# Bankomart.net
KiCad netlist of a schematic drawn in EAGLE
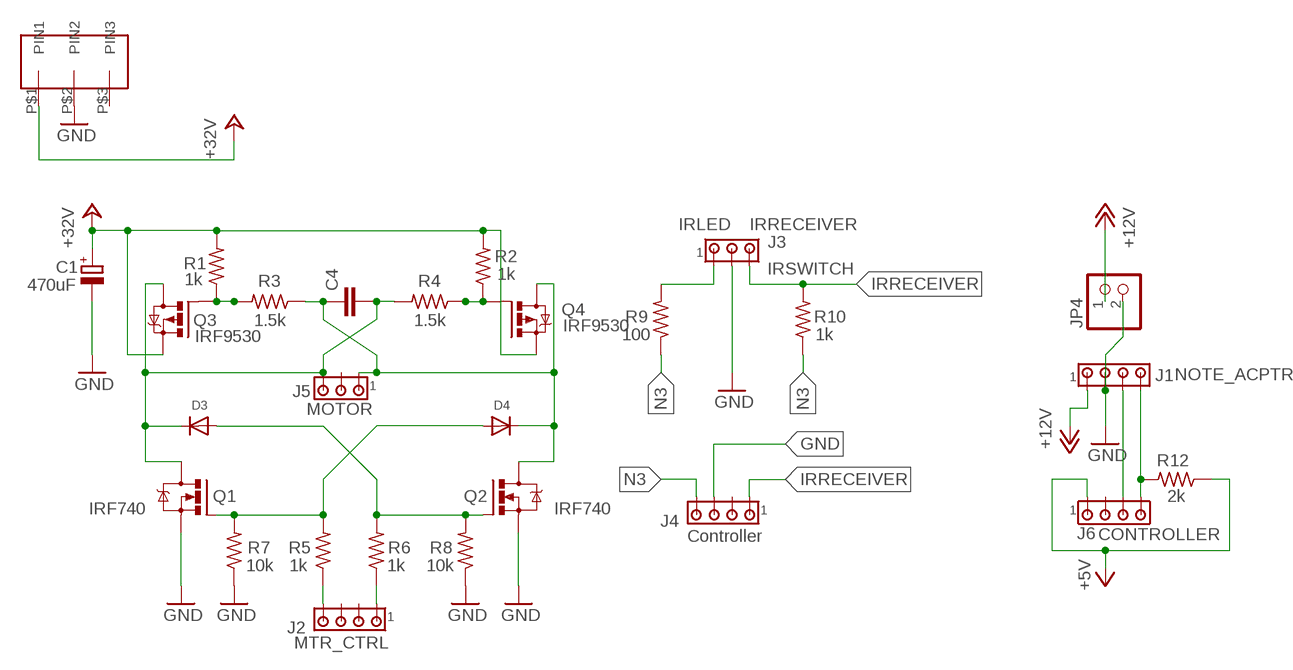
[diagram p0: schematic, sheet 1]

(export (version "E")
  (design (tool "Eeschema 10.0.6"))
  (components
    (comp (ref "C1")
      (value "470uF")
      (footprint "eagle-import:E7,5-18")
      (libsource (lib "eagle-import") (part "CPOL-EUE7.5-18"))
    )
    (comp (ref "C4")
      (value "C-EU050-025X075")
      (footprint "eagle-import:C050-025X075")
      (libsource (lib "eagle-import") (part "C-EU050-025X075"))
    )
    (comp (ref "D3")
      (value "DIODEDO-1N4148")
      (footprint "eagle-import:DO-1N4148")
      (libsource (lib "eagle-import") (part "DIODEDO-1N4148"))
    )
    (comp (ref "D4")
      (value "DIODEDO-1N4148")
      (footprint "eagle-import:DO-1N4148")
      (libsource (lib "eagle-import") (part "DIODEDO-1N4148"))
    )
    (comp (ref "J1")
      (value "NOTE_ACPTR")
      (footprint "eagle-import:10X04MTA")
      (libsource (lib "eagle-import") (part "MTA04-100"))
    )
    (comp (ref "J2")
      (value "MTR_CTRL")
      (footprint "eagle-import:10X04MTA")
      (libsource (lib "eagle-import") (part "MTA04-100"))
    )
    (comp (ref "J3")
      (value "IRSWITCH")
      (footprint "eagle-import:10X03MTA")
      (libsource (lib "eagle-import") (part "MTA03-100"))
    )
    (comp (ref "J4")
      (value "Controller")
      (footprint "eagle-import:10X04MTA")
      (libsource (lib "eagle-import") (part "MTA04-100"))
    )
    (comp (ref "J5")
      (value "MOTOR")
      (footprint "eagle-import:10X03MTA")
      (libsource (lib "eagle-import") (part "MTA03-100"))
    )
    (comp (ref "J6")
      (value "CONTROLLER")
      (footprint "eagle-import:10X04MTA")
      (libsource (lib "eagle-import") (part "MTA04-100"))
    )
    (comp (ref "JP4")
      (value "PINHD-1X2")
      (footprint "eagle-import:1X02")
      (libsource (lib "eagle-import") (part "PINHD-1X2"))
    )
    (comp (ref "Q1")
      (value "IRF740")
      (footprint "eagle-import:TO220BV")
      (libsource (lib "eagle-import") (part "IRF740"))
    )
    (comp (ref "Q2")
      (value "IRF740")
      (footprint "eagle-import:TO220BV")
      (libsource (lib "eagle-import") (part "IRF740"))
    )
    (comp (ref "Q3")
      (value "IRF9530")
      (footprint "eagle-import:TO220BV")
      (libsource (lib "eagle-import") (part "IRF9530"))
    )
    (comp (ref "Q4")
      (value "IRF9530")
      (footprint "eagle-import:TO220BV")
      (libsource (lib "eagle-import") (part "IRF9530"))
    )
    (comp (ref "R1")
      (value "1k")
      (footprint "eagle-import:0207_10")
      (libsource (lib "eagle-import") (part "R-US_0207/10"))
    )
    (comp (ref "R2")
      (value "1k")
      (footprint "eagle-import:0207_10")
      (libsource (lib "eagle-import") (part "R-US_0207/10"))
    )
    (comp (ref "R3")
      (value "1.5k")
      (footprint "eagle-import:0207_10")
      (libsource (lib "eagle-import") (part "R-US_0207/10"))
    )
    (comp (ref "R4")
      (value "1.5k")
      (footprint "eagle-import:0207_10")
      (libsource (lib "eagle-import") (part "R-US_0207/10"))
    )
    (comp (ref "R5")
      (value "1k")
      (footprint "eagle-import:0207_10")
      (libsource (lib "eagle-import") (part "R-US_0207/10"))
    )
    (comp (ref "R6")
      (value "1k")
      (footprint "eagle-import:0207_10")
      (libsource (lib "eagle-import") (part "R-US_0207/10"))
    )
    (comp (ref "R7")
      (value "10k")
      (footprint "eagle-import:0207_10")
      (libsource (lib "eagle-import") (part "R-US_0207/10"))
    )
    (comp (ref "R8")
      (value "10k")
      (footprint "eagle-import:0207_10")
      (libsource (lib "eagle-import") (part "R-US_0207/10"))
    )
    (comp (ref "R9")
      (value "100")
      (footprint "eagle-import:0207_10")
      (libsource (lib "eagle-import") (part "R-US_0207/10"))
    )
    (comp (ref "R10")
      (value "1k")
      (footprint "eagle-import:0207_10")
      (libsource (lib "eagle-import") (part "R-US_0207/10"))
    )
    (comp (ref "R12")
      (value "2k")
      (footprint "eagle-import:0207_10")
      (libsource (lib "eagle-import") (part "R-US_0207/10"))
    )
    (comp (ref "U$1")
      (value "CUSTOM-PIN-3")
      (footprint "eagle-import:CUSTOM-PIN-3")
      (libsource (lib "eagle-import") (part "CUSTOM-PIN-3"))
    )
  )
  (nets
    (net (code "1") (name "+5V") (class "Default")
      (node (ref "J6") (pin "1") (pinfunction "1_1") (pintype "passive"))
      (node (ref "R12") (pin "1") (pinfunction "1_1") (pintype "passive"))
    )
    (net (code "2") (name "+12V") (class "Default")
      (node (ref "J1") (pin "1") (pinfunction "1_1") (pintype "passive"))
      (node (ref "JP4") (pin "1") (pinfunction "1_1") (pintype "passive"))
    )
    (net (code "3") (name "+32V") (class "Default")
      (node (ref "C1") (pin "+") (pinfunction "+_+") (pintype "passive"))
      (node (ref "Q3") (pin "S") (pinfunction "S_S") (pintype "passive"))
      (node (ref "Q4") (pin "S") (pinfunction "S_S") (pintype "passive"))
      (node (ref "R1") (pin "2") (pinfunction "2_2") (pintype "passive"))
      (node (ref "R2") (pin "2") (pinfunction "2_2") (pintype "passive"))
      (node (ref "U$1") (pin "P$1") (pinfunction "PIN1_P$1") (pintype "bidirectional"))
    )
    (net (code "4") (name "/IRLED") (class "Default")
      (node (ref "J3") (pin "1") (pinfunction "1_1") (pintype "passive"))
      (node (ref "R9") (pin "2") (pinfunction "2_2") (pintype "passive"))
    )
    (net (code "5") (name "GND") (class "Default")
      (node (ref "C1") (pin "-") (pinfunction "-_-") (pintype "passive"))
      (node (ref "J1") (pin "2") (pinfunction "2_2") (pintype "passive"))
      (node (ref "J3") (pin "2") (pinfunction "2_2") (pintype "passive"))
      (node (ref "J4") (pin "3") (pinfunction "3_3") (pintype "passive"))
      (node (ref "JP4") (pin "2") (pinfunction "2_2") (pintype "passive"))
      (node (ref "Q1") (pin "S") (pinfunction "S_S") (pintype "passive"))
      (node (ref "Q2") (pin "S") (pinfunction "S_S") (pintype "passive"))
      (node (ref "R7") (pin "1") (pinfunction "1_1") (pintype "passive"))
      (node (ref "R8") (pin "1") (pinfunction "1_1") (pintype "passive"))
      (node (ref "U$1") (pin "P$2") (pinfunction "PIN2_P$2") (pintype "bidirectional"))
    )
    (net (code "6") (name "IRRECEIVER") (class "Default")
      (node (ref "J3") (pin "3") (pinfunction "3_3") (pintype "passive"))
      (node (ref "J4") (pin "1") (pinfunction "1_1") (pintype "passive"))
      (node (ref "R10") (pin "2") (pinfunction "2_2") (pintype "passive"))
    )
    (net (code "7") (name "N3") (class "Default")
      (node (ref "J4") (pin "4") (pinfunction "4_4") (pintype "passive"))
      (node (ref "R10") (pin "1") (pinfunction "1_1") (pintype "passive"))
      (node (ref "R9") (pin "1") (pinfunction "1_1") (pintype "passive"))
    )
    (net (code "8") (name "Net-(C4-Pad1)") (class "Default")
      (node (ref "C4") (pin "1") (pinfunction "1_1") (pintype "passive"))
      (node (ref "D4") (pin "C") (pinfunction "C_C") (pintype "passive"))
      (node (ref "J5") (pin "1") (pinfunction "1_1") (pintype "passive"))
      (node (ref "Q2") (pin "D") (pinfunction "D_D") (pintype "passive"))
      (node (ref "Q4") (pin "D") (pinfunction "D_D") (pintype "passive"))
      (node (ref "R3") (pin "1") (pinfunction "1_1") (pintype "passive"))
    )
    (net (code "9") (name "Net-(C4-Pad2)") (class "Default")
      (node (ref "C4") (pin "2") (pinfunction "2_2") (pintype "passive"))
      (node (ref "D3") (pin "C") (pinfunction "C_C") (pintype "passive"))
      (node (ref "J5") (pin "3") (pinfunction "3_3") (pintype "passive"))
      (node (ref "Q1") (pin "D") (pinfunction "D_D") (pintype "passive"))
      (node (ref "Q3") (pin "D") (pinfunction "D_D") (pintype "passive"))
      (node (ref "R4") (pin "2") (pinfunction "2_2") (pintype "passive"))
    )
    (net (code "10") (name "Net-(D3-PadA)") (class "Default")
      (node (ref "D3") (pin "A") (pinfunction "A_A") (pintype "passive"))
      (node (ref "Q2") (pin "G") (pinfunction "G_G") (pintype "passive"))
      (node (ref "R6") (pin "2") (pinfunction "2_2") (pintype "passive"))
      (node (ref "R8") (pin "2") (pinfunction "2_2") (pintype "passive"))
    )
    (net (code "11") (name "Net-(D4-PadA)") (class "Default")
      (node (ref "D4") (pin "A") (pinfunction "A_A") (pintype "passive"))
      (node (ref "Q1") (pin "G") (pinfunction "G_G") (pintype "passive"))
      (node (ref "R5") (pin "2") (pinfunction "2_2") (pintype "passive"))
      (node (ref "R7") (pin "2") (pinfunction "2_2") (pintype "passive"))
    )
    (net (code "12") (name "Net-(J1-Pad3)") (class "Default")
      (node (ref "J1") (pin "3") (pinfunction "3_3") (pintype "passive"))
      (node (ref "J6") (pin "3") (pinfunction "3_3") (pintype "passive"))
    )
    (net (code "13") (name "Net-(J1-Pad4)") (class "Default")
      (node (ref "J1") (pin "4") (pinfunction "4_4") (pintype "passive"))
      (node (ref "J6") (pin "4") (pinfunction "4_4") (pintype "passive"))
      (node (ref "R12") (pin "2") (pinfunction "2_2") (pintype "passive"))
    )
    (net (code "14") (name "Net-(J2-Pad1)") (class "Default")
      (node (ref "J2") (pin "1") (pinfunction "1_1") (pintype "passive"))
      (node (ref "R6") (pin "1") (pinfunction "1_1") (pintype "passive"))
    )
    (net (code "15") (name "Net-(J2-Pad4)") (class "Default")
      (node (ref "J2") (pin "4") (pinfunction "4_4") (pintype "passive"))
      (node (ref "R5") (pin "1") (pinfunction "1_1") (pintype "passive"))
    )
    (net (code "16") (name "Net-(Q3-PadG)") (class "Default")
      (node (ref "Q3") (pin "G") (pinfunction "G_G") (pintype "passive"))
      (node (ref "R1") (pin "1") (pinfunction "1_1") (pintype "passive"))
      (node (ref "R3") (pin "2") (pinfunction "2_2") (pintype "passive"))
    )
    (net (code "17") (name "Net-(Q4-PadG)") (class "Default")
      (node (ref "Q4") (pin "G") (pinfunction "G_G") (pintype "passive"))
      (node (ref "R2") (pin "1") (pinfunction "1_1") (pintype "passive"))
      (node (ref "R4") (pin "1") (pinfunction "1_1") (pintype "passive"))
    )
    (net (code "18") (name "unconnected-(J2-Pad2)") (class "Default")
      (node (ref "J2") (pin "2") (pinfunction "2_2") (pintype "passive"))
    )
    (net (code "19") (name "unconnected-(J2-Pad3)") (class "Default")
      (node (ref "J2") (pin "3") (pinfunction "3_3") (pintype "passive"))
    )
    (net (code "20") (name "unconnected-(J4-Pad2)") (class "Default")
      (node (ref "J4") (pin "2") (pinfunction "2_2") (pintype "passive"))
    )
    (net (code "21") (name "unconnected-(J5-Pad2)") (class "Default")
      (node (ref "J5") (pin "2") (pinfunction "2_2") (pintype "passive"))
    )
    (net (code "22") (name "unconnected-(J6-Pad2)") (class "Default")
      (node (ref "J6") (pin "2") (pinfunction "2_2") (pintype "passive"))
    )
    (net (code "23") (name "unconnected-(U$1-PIN3-PadP$3)") (class "Default")
      (node (ref "U$1") (pin "P$3") (pinfunction "PIN3_P$3") (pintype "bidirectional"))
    )
  )
)
